# Motors.net
KiCad netlist of a schematic drawn in Altium Designer
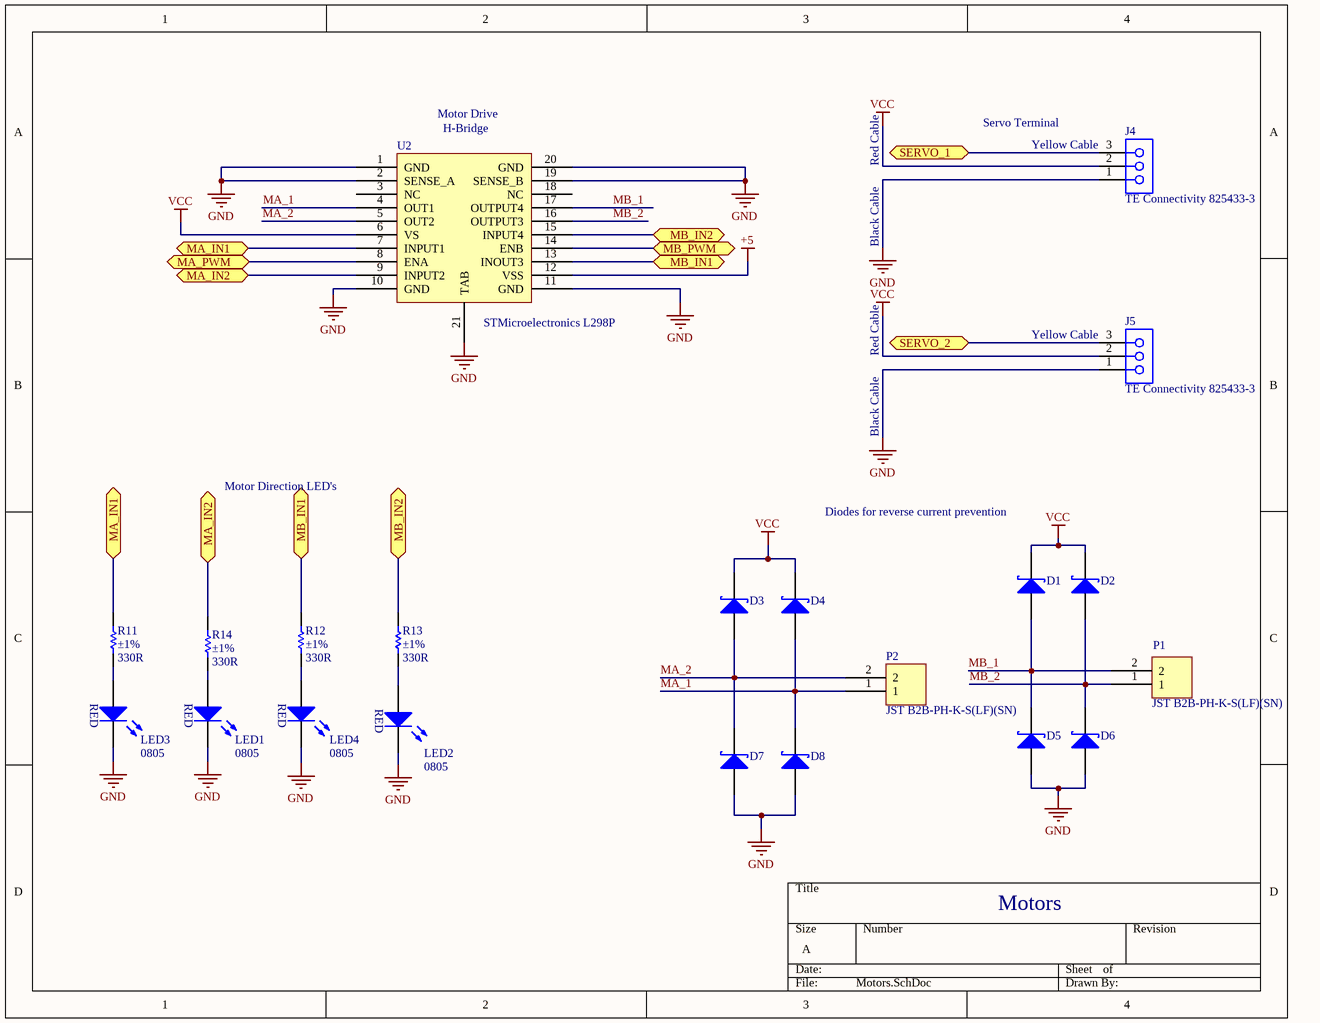
[diagram p0: Motors.SchDoc]

(export (version "E")
  (design (tool "Eeschema 10.0.6"))
  (components
    (comp (ref "D1")
      (value "SS34 SMA DO-214AC")
      (footprint "SMA")
      (description "A Schotty Barrier Rectifier")
      (libsource (lib "CommunityVault") (part "CMP-cx3sevj7k2ks0umzedmk-1"))
    )
    (comp (ref "D2")
      (value "SS34 SMA DO-214AC")
      (footprint "SMA")
      (description "A Schotty Barrier Rectifier")
      (libsource (lib "CommunityVault") (part "CMP-cx3sevj7k2ks0umzedmk-1"))
    )
    (comp (ref "D3")
      (value "SS34 SMA DO-214AC")
      (footprint "SMA")
      (description "A Schotty Barrier Rectifier")
      (libsource (lib "CommunityVault") (part "CMP-cx3sevj7k2ks0umzedmk-1"))
    )
    (comp (ref "D4")
      (value "SS34 SMA DO-214AC")
      (footprint "SMA")
      (description "A Schotty Barrier Rectifier")
      (libsource (lib "CommunityVault") (part "CMP-cx3sevj7k2ks0umzedmk-1"))
    )
    (comp (ref "D5")
      (value "SS34 SMA DO-214AC")
      (footprint "SMA")
      (description "A Schotty Barrier Rectifier")
      (libsource (lib "CommunityVault") (part "CMP-cx3sevj7k2ks0umzedmk-1"))
    )
    (comp (ref "D6")
      (value "SS34 SMA DO-214AC")
      (footprint "SMA")
      (description "A Schotty Barrier Rectifier")
      (libsource (lib "CommunityVault") (part "CMP-cx3sevj7k2ks0umzedmk-1"))
    )
    (comp (ref "D7")
      (value "SS34 SMA DO-214AC")
      (footprint "SMA")
      (description "A Schotty Barrier Rectifier")
      (libsource (lib "CommunityVault") (part "CMP-cx3sevj7k2ks0umzedmk-1"))
    )
    (comp (ref "D8")
      (value "SS34 SMA DO-214AC")
      (footprint "SMA")
      (description "A Schotty Barrier Rectifier")
      (libsource (lib "CommunityVault") (part "CMP-cx3sevj7k2ks0umzedmk-1"))
    )
    (comp (ref "J4")
      (value "TE Connectivity 825433-3")
      (footprint "PCB-43x6b8o6d5mxbq35c0sh-1")
      (description "Pin header; pin strips; AMPMODU MOD II; male; PIN: 3; straight")
      (fields (field (name "MANUFACTURER PART NUMBER") "825433-3"))
      (libsource (lib "CommunityVault") (part "CMP-52d299a8d8748d15-5"))
    )
    (comp (ref "J5")
      (value "TE Connectivity 825433-3")
      (footprint "PCB-43x6b8o6d5mxbq35c0sh-1")
      (description "Pin header; pin strips; AMPMODU MOD II; male; PIN: 3; straight")
      (fields (field (name "MANUFACTURER PART NUMBER") "825433-3"))
      (libsource (lib "CommunityVault") (part "CMP-52d299a8d8748d15-5"))
    )
    (comp (ref "LED1")
      (value "CMP-7f15b6173d91a0d2-5")
      (footprint "LED0805")
      (description "LED; SMD; 0805; red; 7.2-17mcd; 2x1.25mm; 170°; 1.8÷2.6V; 20mA")
      (fields (field (name "CASE/PACKAGE") "0805") (field (name "MANUFACTURER PART NUMBER") "HSMH-C170"))
      (libsource (lib "CommunityVault") (part "CMP-7f15b6173d91a0d2-5"))
    )
    (comp (ref "LED2")
      (value "CMP-7f15b6173d91a0d2-5")
      (footprint "LED0805")
      (description "LED; SMD; 0805; red; 7.2-17mcd; 2x1.25mm; 170°; 1.8÷2.6V; 20mA")
      (fields (field (name "CASE/PACKAGE") "0805") (field (name "MANUFACTURER PART NUMBER") "HSMH-C170"))
      (libsource (lib "CommunityVault") (part "CMP-7f15b6173d91a0d2-5"))
    )
    (comp (ref "LED3")
      (value "CMP-7f15b6173d91a0d2-5")
      (footprint "LED0805")
      (description "LED; SMD; 0805; red; 7.2-17mcd; 2x1.25mm; 170°; 1.8÷2.6V; 20mA")
      (fields (field (name "CASE/PACKAGE") "0805") (field (name "MANUFACTURER PART NUMBER") "HSMH-C170"))
      (libsource (lib "CommunityVault") (part "CMP-7f15b6173d91a0d2-5"))
    )
    (comp (ref "LED4")
      (value "CMP-7f15b6173d91a0d2-5")
      (footprint "LED0805")
      (description "LED; SMD; 0805; red; 7.2-17mcd; 2x1.25mm; 170°; 1.8÷2.6V; 20mA")
      (fields (field (name "CASE/PACKAGE") "0805") (field (name "MANUFACTURER PART NUMBER") "HSMH-C170"))
      (libsource (lib "CommunityVault") (part "CMP-7f15b6173d91a0d2-5"))
    )
    (comp (ref "P1")
      (value "JST B2B-PH-K-S(LF)(SN)")
      (footprint "PCB-gpdi66yn1jko56crxrq7-1")
      (description "PH Series 2 Position 2 mm Pitch Through Hole Top Entry Shrouded Header")
      (fields (field (name "MANUFACTURER PART NUMBER") "B2B-PH-K-S(LF)(SN)"))
      (libsource (lib "CommunityVault") (part "SYM-c32e0a272a631ce9-1"))
    )
    (comp (ref "P2")
      (value "JST B2B-PH-K-S(LF)(SN)")
      (footprint "PCB-gpdi66yn1jko56crxrq7-1")
      (description "PH Series 2 Position 2 mm Pitch Through Hole Top Entry Shrouded Header")
      (fields (field (name "MANUFACTURER PART NUMBER") "B2B-PH-K-S(LF)(SN)"))
      (libsource (lib "CommunityVault") (part "SYM-c32e0a272a631ce9-1"))
    )
    (comp (ref "R11")
      (value "Bourns CR0805-FX-4701GLF")
      (footprint "PCB-4097432-1")
      (description "Res Thick Film 0805 4.7K Ohm 1% 1/8W ±100ppm/°C Molded SMD SMD Paper Tape on Plastic Reel")
      (fields
        (field (name "MANUFACTURER PART NUMBER") "CR0805-FX-4701GLF")
        (field (name "RESISTANCE TOLERANCE") "±1%")
        (field (name "RESISTANCE") "330R")
      )
      (libsource (lib "CommunityVault") (part "CMP-97505e06006c4897-1"))
    )
    (comp (ref "R12")
      (value "Bourns CR0805-FX-4701GLF")
      (footprint "PCB-4097432-1")
      (description "Res Thick Film 0805 4.7K Ohm 1% 1/8W ±100ppm/°C Molded SMD SMD Paper Tape on Plastic Reel")
      (fields
        (field (name "MANUFACTURER PART NUMBER") "CR0805-FX-4701GLF")
        (field (name "RESISTANCE TOLERANCE") "±1%")
        (field (name "RESISTANCE") "330R")
      )
      (libsource (lib "CommunityVault") (part "CMP-97505e06006c4897-1"))
    )
    (comp (ref "R13")
      (value "Bourns CR0805-FX-4701GLF")
      (footprint "PCB-4097432-1")
      (description "Res Thick Film 0805 4.7K Ohm 1% 1/8W ±100ppm/°C Molded SMD SMD Paper Tape on Plastic Reel")
      (fields
        (field (name "MANUFACTURER PART NUMBER") "CR0805-FX-4701GLF")
        (field (name "RESISTANCE TOLERANCE") "±1%")
        (field (name "RESISTANCE") "330R")
      )
      (libsource (lib "CommunityVault") (part "CMP-97505e06006c4897-1"))
    )
    (comp (ref "R14")
      (value "Bourns CR0805-FX-4701GLF")
      (footprint "PCB-4097432-1")
      (description "Res Thick Film 0805 4.7K Ohm 1% 1/8W ±100ppm/°C Molded SMD SMD Paper Tape on Plastic Reel")
      (fields
        (field (name "MANUFACTURER PART NUMBER") "CR0805-FX-4701GLF")
        (field (name "RESISTANCE TOLERANCE") "±1%")
        (field (name "RESISTANCE") "330R")
      )
      (libsource (lib "CommunityVault") (part "CMP-97505e06006c4897-1"))
    )
    (comp (ref "U2")
      (value "STMicroelectronics L298P")
      (footprint "L298PSOIC127P1420X360-20N")
      (description "L298 Series Dual Full Bridge 4 A 46 V Driver Surface Mount - PowerSO-20")
      (fields (field (name "MANUFACTURER PART NUMBER") "L298P"))
      (libsource (lib "CommunityVault") (part "CMP-1433026-16"))
    )
  )
  (nets
    (net (code "1") (name "+5") (class "Default")
      (node (ref "U2") (pin "12") (pinfunction "VSS_12") (pintype "passive"))
    )
    (net (code "2") (name "/MA_1") (class "Default")
      (node (ref "D4") (pin "1") (pinfunction "A_1") (pintype "passive"))
      (node (ref "D8") (pin "2") (pinfunction "K_2") (pintype "passive"))
      (node (ref "P2") (pin "1") (pinfunction "1_1") (pintype "passive"))
      (node (ref "U2") (pin "4") (pinfunction "OUT1_4") (pintype "passive"))
    )
    (net (code "3") (name "/MA_2") (class "Default")
      (node (ref "D3") (pin "1") (pinfunction "A_1") (pintype "passive"))
      (node (ref "D7") (pin "2") (pinfunction "K_2") (pintype "passive"))
      (node (ref "P2") (pin "2") (pinfunction "2_2") (pintype "passive"))
      (node (ref "U2") (pin "5") (pinfunction "OUT2_5") (pintype "passive"))
    )
    (net (code "4") (name "/MA_IN1") (class "Default")
      (node (ref "R11") (pin "2") (pinfunction "2_2") (pintype "passive"))
      (node (ref "U2") (pin "7") (pinfunction "INPUT1_7") (pintype "passive"))
    )
    (net (code "5") (name "/MA_IN2") (class "Default")
      (node (ref "R14") (pin "2") (pinfunction "2_2") (pintype "passive"))
      (node (ref "U2") (pin "9") (pinfunction "INPUT2_9") (pintype "passive"))
    )
    (net (code "6") (name "/MA_PWM") (class "Default")
      (node (ref "U2") (pin "8") (pinfunction "ENA_8") (pintype "passive"))
    )
    (net (code "7") (name "/MB_1") (class "Default")
      (node (ref "D1") (pin "1") (pinfunction "A_1") (pintype "passive"))
      (node (ref "D5") (pin "2") (pinfunction "K_2") (pintype "passive"))
      (node (ref "P1") (pin "2") (pinfunction "2_2") (pintype "passive"))
      (node (ref "U2") (pin "17") (pinfunction "OUTPUT4_17") (pintype "passive"))
    )
    (net (code "8") (name "/MB_2") (class "Default")
      (node (ref "D2") (pin "1") (pinfunction "A_1") (pintype "passive"))
      (node (ref "D6") (pin "2") (pinfunction "K_2") (pintype "passive"))
      (node (ref "P1") (pin "1") (pinfunction "1_1") (pintype "passive"))
      (node (ref "U2") (pin "16") (pinfunction "OUTPUT3_16") (pintype "passive"))
    )
    (net (code "9") (name "/MB_IN1") (class "Default")
      (node (ref "R12") (pin "2") (pinfunction "2_2") (pintype "passive"))
      (node (ref "U2") (pin "13") (pinfunction "INOUT3_13") (pintype "passive"))
    )
    (net (code "10") (name "/MB_IN2") (class "Default")
      (node (ref "R13") (pin "2") (pinfunction "2_2") (pintype "passive"))
      (node (ref "U2") (pin "15") (pinfunction "INPUT4_15") (pintype "passive"))
    )
    (net (code "11") (name "/MB_PWM") (class "Default")
      (node (ref "U2") (pin "14") (pinfunction "ENB_14") (pintype "passive"))
    )
    (net (code "12") (name "/SERVO_1") (class "Default")
      (node (ref "J4") (pin "3") (pinfunction "3_3") (pintype "passive"))
    )
    (net (code "13") (name "/SERVO_2") (class "Default")
      (node (ref "J5") (pin "3") (pinfunction "3_3") (pintype "passive"))
    )
    (net (code "14") (name "GND") (class "Default")
      (node (ref "D5") (pin "1") (pinfunction "A_1") (pintype "passive"))
      (node (ref "D6") (pin "1") (pinfunction "A_1") (pintype "passive"))
      (node (ref "D7") (pin "1") (pinfunction "A_1") (pintype "passive"))
      (node (ref "D8") (pin "1") (pinfunction "A_1") (pintype "passive"))
      (node (ref "J4") (pin "1") (pinfunction "1_1") (pintype "passive"))
      (node (ref "J5") (pin "1") (pinfunction "1_1") (pintype "passive"))
      (node (ref "LED1") (pin "1") (pinfunction "K_1") (pintype "passive"))
      (node (ref "LED2") (pin "1") (pinfunction "K_1") (pintype "passive"))
      (node (ref "LED3") (pin "1") (pinfunction "K_1") (pintype "passive"))
      (node (ref "LED4") (pin "1") (pinfunction "K_1") (pintype "passive"))
      (node (ref "U2") (pin "1") (pinfunction "GND_1") (pintype "passive"))
      (node (ref "U2") (pin "10") (pinfunction "GND_10") (pintype "passive"))
      (node (ref "U2") (pin "11") (pinfunction "GND_11") (pintype "passive"))
      (node (ref "U2") (pin "19") (pinfunction "SENSE_B_19") (pintype "passive"))
      (node (ref "U2") (pin "2") (pinfunction "SENSE_A_2") (pintype "passive"))
      (node (ref "U2") (pin "20") (pinfunction "GND_20") (pintype "passive"))
      (node (ref "U2") (pin "21") (pinfunction "TAB_21") (pintype "power_in"))
    )
    (net (code "15") (name "Net-(LED1-A)") (class "Default")
      (node (ref "LED1") (pin "2") (pinfunction "A_2") (pintype "passive"))
      (node (ref "R14") (pin "1") (pinfunction "1_1") (pintype "passive"))
    )
    (net (code "16") (name "Net-(LED2-A)") (class "Default")
      (node (ref "LED2") (pin "2") (pinfunction "A_2") (pintype "passive"))
      (node (ref "R13") (pin "1") (pinfunction "1_1") (pintype "passive"))
    )
    (net (code "17") (name "Net-(LED3-A)") (class "Default")
      (node (ref "LED3") (pin "2") (pinfunction "A_2") (pintype "passive"))
      (node (ref "R11") (pin "1") (pinfunction "1_1") (pintype "passive"))
    )
    (net (code "18") (name "Net-(LED4-A)") (class "Default")
      (node (ref "LED4") (pin "2") (pinfunction "A_2") (pintype "passive"))
      (node (ref "R12") (pin "1") (pinfunction "1_1") (pintype "passive"))
    )
    (net (code "19") (name "VCC") (class "Default")
      (node (ref "D1") (pin "2") (pinfunction "K_2") (pintype "passive"))
      (node (ref "D2") (pin "2") (pinfunction "K_2") (pintype "passive"))
      (node (ref "D3") (pin "2") (pinfunction "K_2") (pintype "passive"))
      (node (ref "D4") (pin "2") (pinfunction "K_2") (pintype "passive"))
      (node (ref "J4") (pin "2") (pinfunction "2_2") (pintype "passive"))
      (node (ref "J5") (pin "2") (pinfunction "2_2") (pintype "passive"))
      (node (ref "U2") (pin "6") (pinfunction "VS_6") (pintype "passive"))
    )
    (net (code "20") (name "unconnected-(U2-NC-Pad3)") (class "Default")
      (node (ref "U2") (pin "3") (pinfunction "NC_3") (pintype "passive"))
    )
    (net (code "21") (name "unconnected-(U2-NC-Pad18)") (class "Default")
      (node (ref "U2") (pin "18") (pinfunction "NC_18") (pintype "passive"))
    )
  )
)
